# LED-Cube_Platine.net
KiCad netlist of a schematic drawn in EAGLE
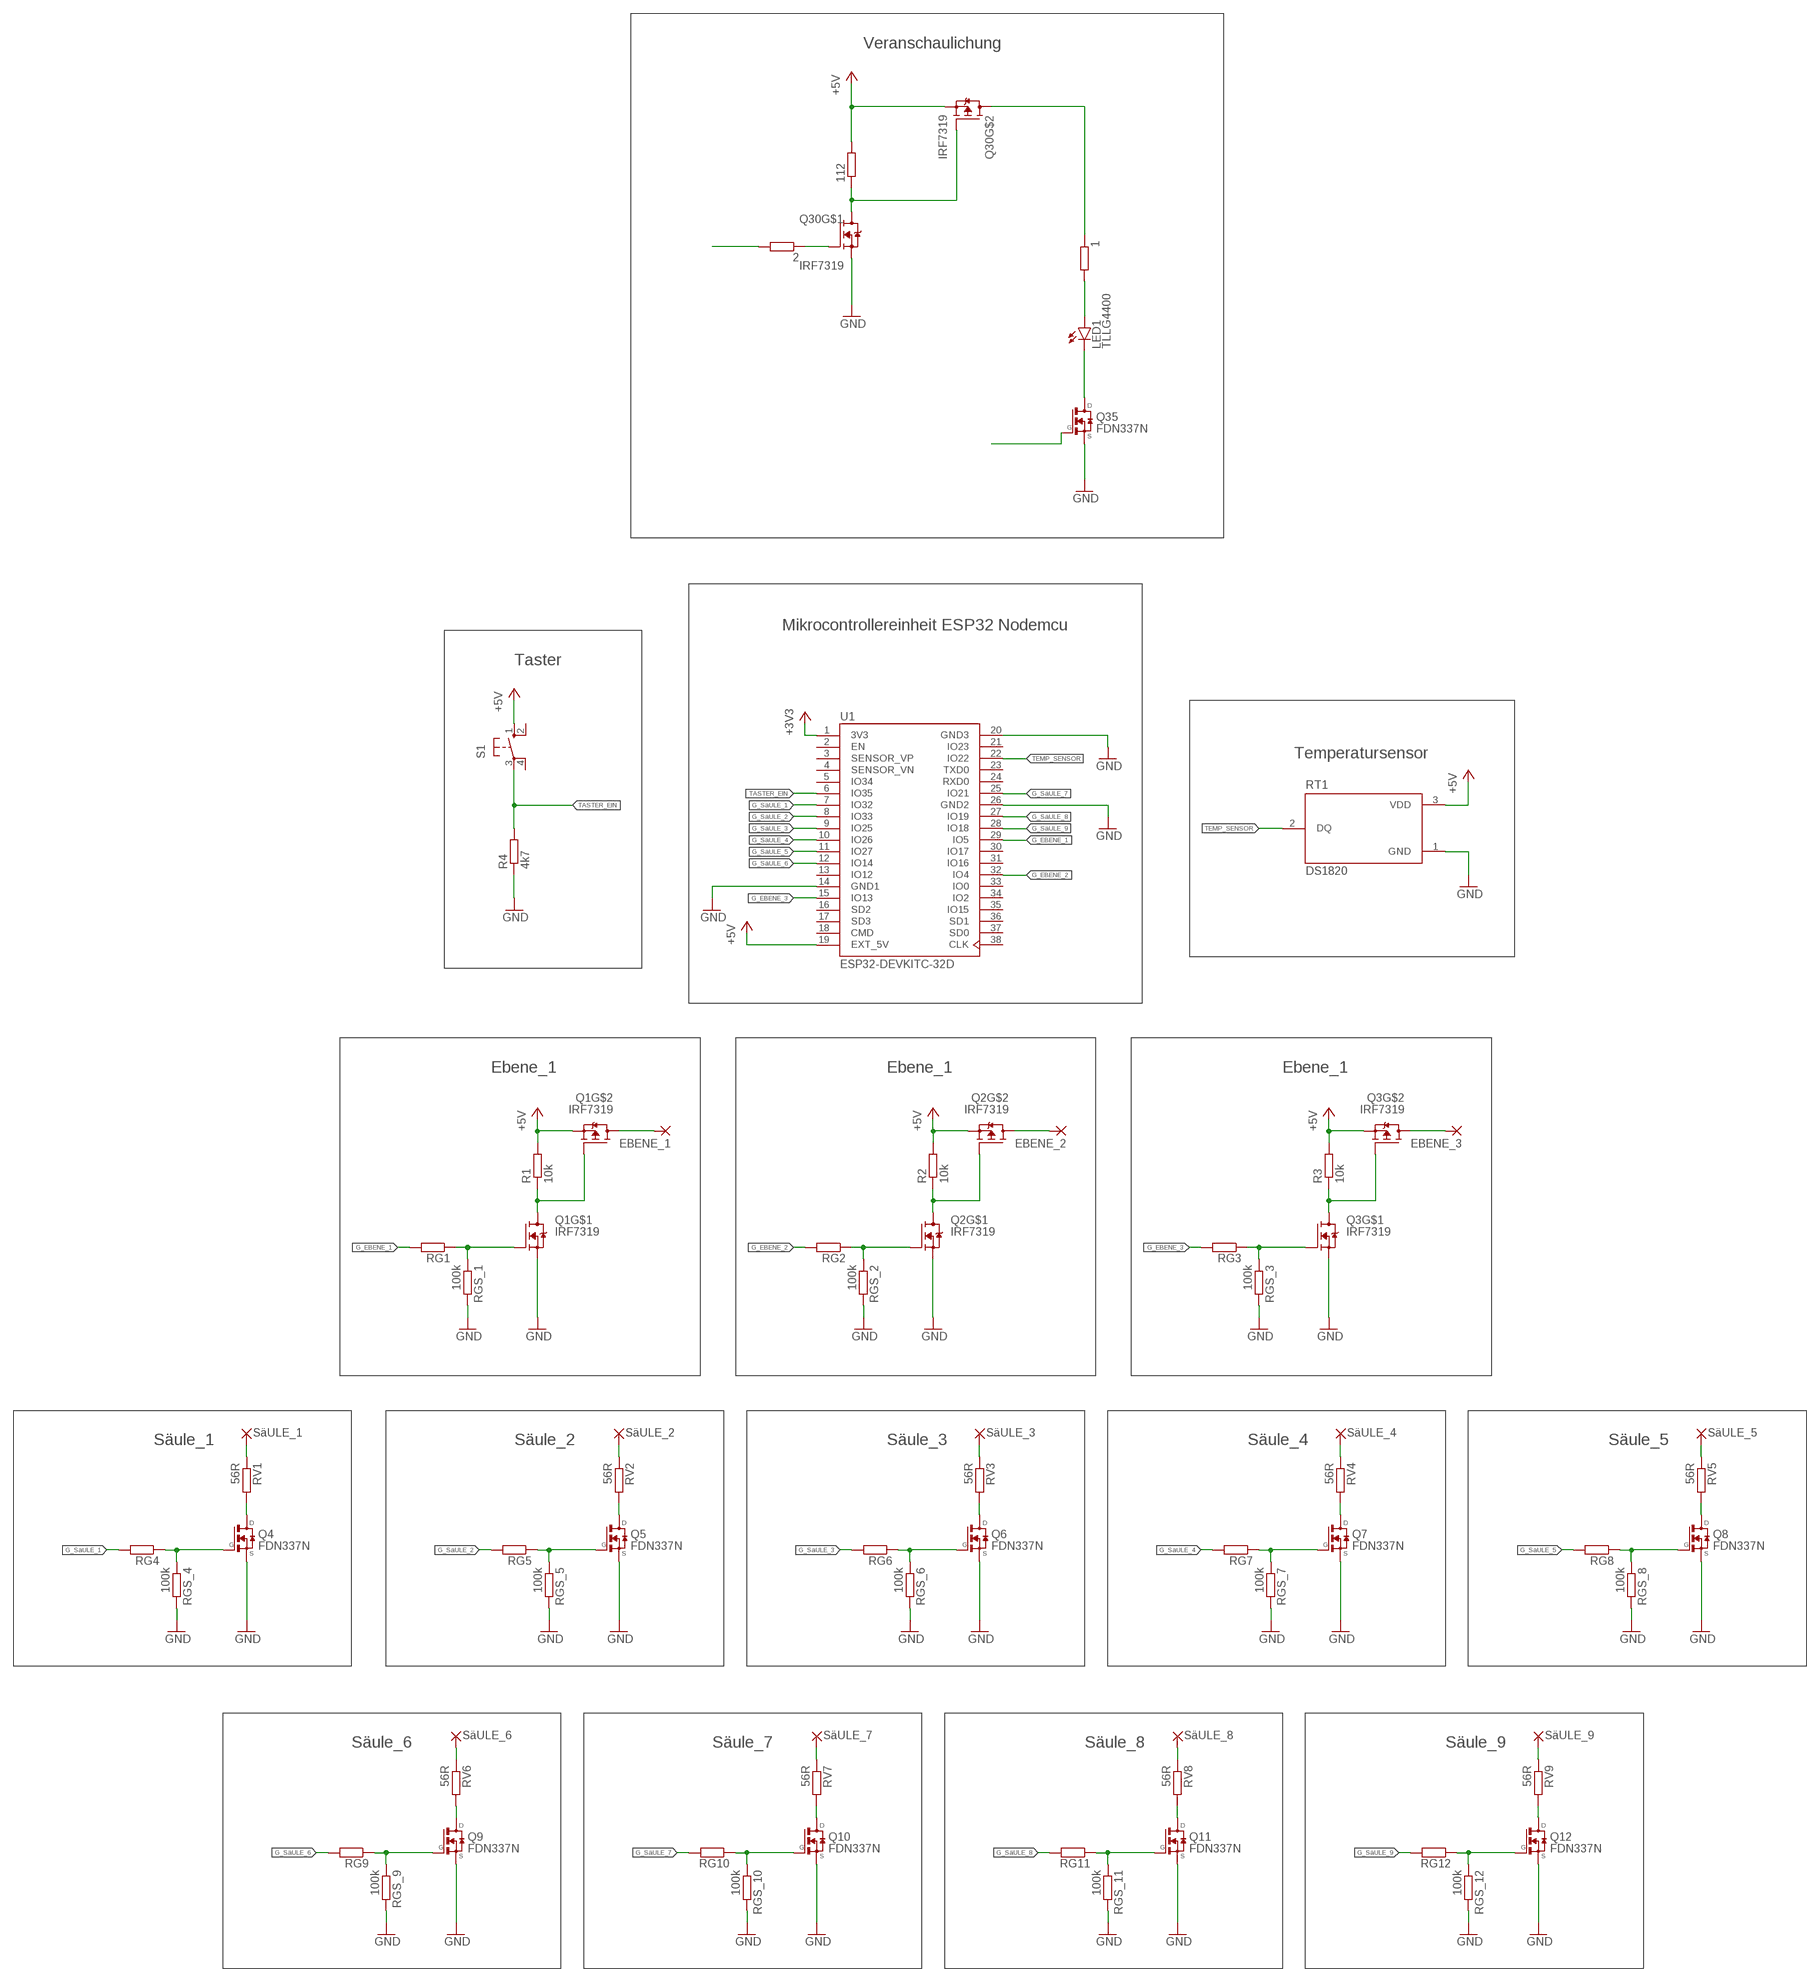
[diagram p0: schematic, sheet 1]

(export (version "E")
  (design (tool "Eeschema 10.0.6"))
  (components
    (comp (ref "1")
      (value "R-EU_R0805")
      (footprint "eagle-import:R0805")
      (libsource (lib "eagle-import") (part "R-EU_R0805"))
    )
    (comp (ref "2")
      (value "R-EU_R0805")
      (footprint "eagle-import:R0805")
      (libsource (lib "eagle-import") (part "R-EU_R0805"))
    )
    (comp (ref "112")
      (value "R-EU_R0805")
      (footprint "eagle-import:R0805")
      (libsource (lib "eagle-import") (part "R-EU_R0805"))
    )
    (comp (ref "EBENE_1")
      (value "WIREPAD1,6/0,8")
      (footprint "eagle-import:1,6_0,8")
      (libsource (lib "eagle-import") (part "WIREPAD1,6/0,8"))
    )
    (comp (ref "EBENE_2")
      (value "WIREPAD1,6/0,8")
      (footprint "eagle-import:1,6_0,8")
      (libsource (lib "eagle-import") (part "WIREPAD1,6/0,8"))
    )
    (comp (ref "EBENE_3")
      (value "WIREPAD1,6/0,8")
      (footprint "eagle-import:1,6_0,8")
      (libsource (lib "eagle-import") (part "WIREPAD1,6/0,8"))
    )
    (comp (ref "LED1")
      (value "TLLG4400")
      (footprint "eagle-import:LED3MM")
      (fields (field (name "MF") "VISHAY SEMICONDUCTOR"))
      (libsource (lib "eagle-import") (part "TLLG4400"))
    )
    (comp (ref "Q1")
      (value "IRF7319")
      (footprint "eagle-import:SOIC127P600X175-8N")
      (fields (field (name "MF") "Infineon Technologies"))
      (libsource (lib "eagle-import") (part "IRF7319"))
    )
    (comp (ref "Q2")
      (value "IRF7319")
      (footprint "eagle-import:SOIC127P600X175-8N")
      (fields (field (name "MF") "Infineon Technologies"))
      (libsource (lib "eagle-import") (part "IRF7319"))
    )
    (comp (ref "Q3")
      (value "IRF7319")
      (footprint "eagle-import:SOIC127P600X175-8N")
      (fields (field (name "MF") "Infineon Technologies"))
      (libsource (lib "eagle-import") (part "IRF7319"))
    )
    (comp (ref "Q4")
      (value "FDN337N")
      (footprint "eagle-import:SSOT-3")
      (fields (field (name "MF") "ON Semiconductor"))
      (libsource (lib "eagle-import") (part "FDN337N"))
    )
    (comp (ref "Q5")
      (value "FDN337N")
      (footprint "eagle-import:SSOT-3")
      (fields (field (name "MF") "ON Semiconductor"))
      (libsource (lib "eagle-import") (part "FDN337N"))
    )
    (comp (ref "Q6")
      (value "FDN337N")
      (footprint "eagle-import:SSOT-3")
      (fields (field (name "MF") "ON Semiconductor"))
      (libsource (lib "eagle-import") (part "FDN337N"))
    )
    (comp (ref "Q7")
      (value "FDN337N")
      (footprint "eagle-import:SSOT-3")
      (fields (field (name "MF") "ON Semiconductor"))
      (libsource (lib "eagle-import") (part "FDN337N"))
    )
    (comp (ref "Q8")
      (value "FDN337N")
      (footprint "eagle-import:SSOT-3")
      (fields (field (name "MF") "ON Semiconductor"))
      (libsource (lib "eagle-import") (part "FDN337N"))
    )
    (comp (ref "Q9")
      (value "FDN337N")
      (footprint "eagle-import:SSOT-3")
      (fields (field (name "MF") "ON Semiconductor"))
      (libsource (lib "eagle-import") (part "FDN337N"))
    )
    (comp (ref "Q10")
      (value "FDN337N")
      (footprint "eagle-import:SSOT-3")
      (fields (field (name "MF") "ON Semiconductor"))
      (libsource (lib "eagle-import") (part "FDN337N"))
    )
    (comp (ref "Q11")
      (value "FDN337N")
      (footprint "eagle-import:SSOT-3")
      (fields (field (name "MF") "ON Semiconductor"))
      (libsource (lib "eagle-import") (part "FDN337N"))
    )
    (comp (ref "Q12")
      (value "FDN337N")
      (footprint "eagle-import:SSOT-3")
      (fields (field (name "MF") "ON Semiconductor"))
      (libsource (lib "eagle-import") (part "FDN337N"))
    )
    (comp (ref "Q30")
      (value "IRF7319")
      (footprint "eagle-import:SOIC127P600X175-8N")
      (fields (field (name "MF") "Infineon Technologies"))
      (libsource (lib "eagle-import") (part "IRF7319"))
    )
    (comp (ref "Q35")
      (value "FDN337N")
      (footprint "eagle-import:SSOT-3")
      (fields (field (name "MF") "ON Semiconductor"))
      (libsource (lib "eagle-import") (part "FDN337N"))
    )
    (comp (ref "R1")
      (value "10k")
      (footprint "eagle-import:R0805")
      (libsource (lib "eagle-import") (part "R-EU_R0805"))
    )
    (comp (ref "R2")
      (value "10k")
      (footprint "eagle-import:R0805")
      (libsource (lib "eagle-import") (part "R-EU_R0805"))
    )
    (comp (ref "R3")
      (value "10k")
      (footprint "eagle-import:R0805")
      (libsource (lib "eagle-import") (part "R-EU_R0805"))
    )
    (comp (ref "R4")
      (value "4k7")
      (footprint "eagle-import:R0805")
      (libsource (lib "eagle-import") (part "R-EU_R0805"))
    )
    (comp (ref "RG1")
      (value "R-EU_R0805")
      (footprint "eagle-import:R0805")
      (libsource (lib "eagle-import") (part "R-EU_R0805"))
    )
    (comp (ref "RG2")
      (value "R-EU_R0805")
      (footprint "eagle-import:R0805")
      (libsource (lib "eagle-import") (part "R-EU_R0805"))
    )
    (comp (ref "RG3")
      (value "R-EU_R0805")
      (footprint "eagle-import:R0805")
      (libsource (lib "eagle-import") (part "R-EU_R0805"))
    )
    (comp (ref "RG4")
      (value "R-EU_R0805")
      (footprint "eagle-import:R0805")
      (libsource (lib "eagle-import") (part "R-EU_R0805"))
    )
    (comp (ref "RG5")
      (value "R-EU_R0805")
      (footprint "eagle-import:R0805")
      (libsource (lib "eagle-import") (part "R-EU_R0805"))
    )
    (comp (ref "RG6")
      (value "R-EU_R0805")
      (footprint "eagle-import:R0805")
      (libsource (lib "eagle-import") (part "R-EU_R0805"))
    )
    (comp (ref "RG7")
      (value "R-EU_R0805")
      (footprint "eagle-import:R0805")
      (libsource (lib "eagle-import") (part "R-EU_R0805"))
    )
    (comp (ref "RG8")
      (value "R-EU_R0805")
      (footprint "eagle-import:R0805")
      (libsource (lib "eagle-import") (part "R-EU_R0805"))
    )
    (comp (ref "RG9")
      (value "R-EU_R0805")
      (footprint "eagle-import:R0805")
      (libsource (lib "eagle-import") (part "R-EU_R0805"))
    )
    (comp (ref "RG10")
      (value "R-EU_R0805")
      (footprint "eagle-import:R0805")
      (libsource (lib "eagle-import") (part "R-EU_R0805"))
    )
    (comp (ref "RG11")
      (value "R-EU_R0805")
      (footprint "eagle-import:R0805")
      (libsource (lib "eagle-import") (part "R-EU_R0805"))
    )
    (comp (ref "RG12")
      (value "R-EU_R0805")
      (footprint "eagle-import:R0805")
      (libsource (lib "eagle-import") (part "R-EU_R0805"))
    )
    (comp (ref "RGS_1")
      (value "100k")
      (footprint "eagle-import:R0805")
      (libsource (lib "eagle-import") (part "R-EU_R0805"))
    )
    (comp (ref "RGS_2")
      (value "100k")
      (footprint "eagle-import:R0805")
      (libsource (lib "eagle-import") (part "R-EU_R0805"))
    )
    (comp (ref "RGS_3")
      (value "100k")
      (footprint "eagle-import:R0805")
      (libsource (lib "eagle-import") (part "R-EU_R0805"))
    )
    (comp (ref "RGS_4")
      (value "100k")
      (footprint "eagle-import:R0805")
      (libsource (lib "eagle-import") (part "R-EU_R0805"))
    )
    (comp (ref "RGS_5")
      (value "100k")
      (footprint "eagle-import:R0805")
      (libsource (lib "eagle-import") (part "R-EU_R0805"))
    )
    (comp (ref "RGS_6")
      (value "100k")
      (footprint "eagle-import:R0805")
      (libsource (lib "eagle-import") (part "R-EU_R0805"))
    )
    (comp (ref "RGS_7")
      (value "100k")
      (footprint "eagle-import:R0805")
      (libsource (lib "eagle-import") (part "R-EU_R0805"))
    )
    (comp (ref "RGS_8")
      (value "100k")
      (footprint "eagle-import:R0805")
      (libsource (lib "eagle-import") (part "R-EU_R0805"))
    )
    (comp (ref "RGS_9")
      (value "100k")
      (footprint "eagle-import:R0805")
      (libsource (lib "eagle-import") (part "R-EU_R0805"))
    )
    (comp (ref "RGS_10")
      (value "100k")
      (footprint "eagle-import:R0805")
      (libsource (lib "eagle-import") (part "R-EU_R0805"))
    )
    (comp (ref "RGS_11")
      (value "100k")
      (footprint "eagle-import:R0805")
      (libsource (lib "eagle-import") (part "R-EU_R0805"))
    )
    (comp (ref "RGS_12")
      (value "100k")
      (footprint "eagle-import:R0805")
      (libsource (lib "eagle-import") (part "R-EU_R0805"))
    )
    (comp (ref "RT1")
      (value "DS1820")
      (footprint "eagle-import:TO92127P495H695-3")
      (fields (field (name "MF") "Maxim Integrated"))
      (libsource (lib "eagle-import") (part "DS1820"))
    )
    (comp (ref "RV1")
      (value "56R")
      (footprint "eagle-import:R0805")
      (libsource (lib "eagle-import") (part "R-EU_R0805"))
    )
    (comp (ref "RV2")
      (value "56R")
      (footprint "eagle-import:R0805")
      (libsource (lib "eagle-import") (part "R-EU_R0805"))
    )
    (comp (ref "RV3")
      (value "56R")
      (footprint "eagle-import:R0805")
      (libsource (lib "eagle-import") (part "R-EU_R0805"))
    )
    (comp (ref "RV4")
      (value "56R")
      (footprint "eagle-import:R0805")
      (libsource (lib "eagle-import") (part "R-EU_R0805"))
    )
    (comp (ref "RV5")
      (value "56R")
      (footprint "eagle-import:R0805")
      (libsource (lib "eagle-import") (part "R-EU_R0805"))
    )
    (comp (ref "RV6")
      (value "56R")
      (footprint "eagle-import:R0805")
      (libsource (lib "eagle-import") (part "R-EU_R0805"))
    )
    (comp (ref "RV7")
      (value "56R")
      (footprint "eagle-import:R0805")
      (libsource (lib "eagle-import") (part "R-EU_R0805"))
    )
    (comp (ref "RV8")
      (value "56R")
      (footprint "eagle-import:R0805")
      (libsource (lib "eagle-import") (part "R-EU_R0805"))
    )
    (comp (ref "RV9")
      (value "56R")
      (footprint "eagle-import:R0805")
      (libsource (lib "eagle-import") (part "R-EU_R0805"))
    )
    (comp (ref "S1")
      (value "10-XX")
      (footprint "eagle-import:B3F-10XX")
      (fields (field (name "MPN") "B3F-1000"))
      (libsource (lib "eagle-import") (part "10-XX"))
    )
    (comp (ref "SäULE_1")
      (value "WIREPAD1,6/0,8")
      (footprint "eagle-import:1,6_0,8")
      (libsource (lib "eagle-import") (part "WIREPAD1,6/0,8"))
    )
    (comp (ref "SäULE_2")
      (value "WIREPAD1,6/0,8")
      (footprint "eagle-import:1,6_0,8")
      (libsource (lib "eagle-import") (part "WIREPAD1,6/0,8"))
    )
    (comp (ref "SäULE_3")
      (value "WIREPAD1,6/0,8")
      (footprint "eagle-import:1,6_0,8")
      (libsource (lib "eagle-import") (part "WIREPAD1,6/0,8"))
    )
    (comp (ref "SäULE_4")
      (value "WIREPAD1,6/0,8")
      (footprint "eagle-import:1,6_0,8")
      (libsource (lib "eagle-import") (part "WIREPAD1,6/0,8"))
    )
    (comp (ref "SäULE_5")
      (value "WIREPAD1,6/0,8")
      (footprint "eagle-import:1,6_0,8")
      (libsource (lib "eagle-import") (part "WIREPAD1,6/0,8"))
    )
    (comp (ref "SäULE_6")
      (value "WIREPAD1,6/0,8")
      (footprint "eagle-import:1,6_0,8")
      (libsource (lib "eagle-import") (part "WIREPAD1,6/0,8"))
    )
    (comp (ref "SäULE_7")
      (value "WIREPAD1,6/0,8")
      (footprint "eagle-import:1,6_0,8")
      (libsource (lib "eagle-import") (part "WIREPAD1,6/0,8"))
    )
    (comp (ref "SäULE_8")
      (value "WIREPAD1,6/0,8")
      (footprint "eagle-import:1,6_0,8")
      (libsource (lib "eagle-import") (part "WIREPAD1,6/0,8"))
    )
    (comp (ref "SäULE_9")
      (value "WIREPAD1,6/0,8")
      (footprint "eagle-import:1,6_0,8")
      (libsource (lib "eagle-import") (part "WIREPAD1,6/0,8"))
    )
    (comp (ref "U1")
      (value "ESP32-DEVKITC-32D")
      (footprint "eagle-import:MODULE_ESP32-DEVKITC-32D")
      (fields (field (name "MF") "Espressif Systems"))
      (libsource (lib "eagle-import") (part "ESP32-DEVKITC-32D"))
    )
  )
  (nets
    (net (code "1") (name "+3V3") (class "Default")
      (node (ref "U1") (pin "1") (pinfunction "3V3_1") (pintype "power_in"))
    )
    (net (code "2") (name "+5V") (class "Default")
      (node (ref "112") (pin "2") (pinfunction "2_2") (pintype "passive"))
      (node (ref "Q1") (pin "3") (pinfunction "S2_3") (pintype "passive"))
      (node (ref "Q2") (pin "3") (pinfunction "S2_3") (pintype "passive"))
      (node (ref "Q3") (pin "3") (pinfunction "S2_3") (pintype "passive"))
      (node (ref "Q30") (pin "3") (pinfunction "S2_3") (pintype "passive"))
      (node (ref "R1") (pin "2") (pinfunction "2_2") (pintype "passive"))
      (node (ref "R2") (pin "2") (pinfunction "2_2") (pintype "passive"))
      (node (ref "R3") (pin "2") (pinfunction "2_2") (pintype "passive"))
      (node (ref "RT1") (pin "3") (pinfunction "VDD_3") (pintype "power_in"))
      (node (ref "S1") (pin "1") (pinfunction "S_1") (pintype "passive"))
      (node (ref "U1") (pin "19") (pinfunction "EXT_5V_19") (pintype "power_in"))
    )
    (net (code "3") (name "GND") (class "Default")
      (node (ref "Q1") (pin "1") (pinfunction "S1_1") (pintype "passive"))
      (node (ref "Q10") (pin "2") (pinfunction "S_2") (pintype "passive"))
      (node (ref "Q11") (pin "2") (pinfunction "S_2") (pintype "passive"))
      (node (ref "Q12") (pin "2") (pinfunction "S_2") (pintype "passive"))
      (node (ref "Q2") (pin "1") (pinfunction "S1_1") (pintype "passive"))
      (node (ref "Q3") (pin "1") (pinfunction "S1_1") (pintype "passive"))
      (node (ref "Q30") (pin "1") (pinfunction "S1_1") (pintype "passive"))
      (node (ref "Q35") (pin "2") (pinfunction "S_2") (pintype "passive"))
      (node (ref "Q4") (pin "2") (pinfunction "S_2") (pintype "passive"))
      (node (ref "Q5") (pin "2") (pinfunction "S_2") (pintype "passive"))
      (node (ref "Q6") (pin "2") (pinfunction "S_2") (pintype "passive"))
      (node (ref "Q7") (pin "2") (pinfunction "S_2") (pintype "passive"))
      (node (ref "Q8") (pin "2") (pinfunction "S_2") (pintype "passive"))
      (node (ref "Q9") (pin "2") (pinfunction "S_2") (pintype "passive"))
      (node (ref "R4") (pin "1") (pinfunction "1_1") (pintype "passive"))
      (node (ref "RGS_1") (pin "2") (pinfunction "2_2") (pintype "passive"))
      (node (ref "RGS_10") (pin "2") (pinfunction "2_2") (pintype "passive"))
      (node (ref "RGS_11") (pin "2") (pinfunction "2_2") (pintype "passive"))
      (node (ref "RGS_12") (pin "2") (pinfunction "2_2") (pintype "passive"))
      (node (ref "RGS_2") (pin "2") (pinfunction "2_2") (pintype "passive"))
      (node (ref "RGS_3") (pin "2") (pinfunction "2_2") (pintype "passive"))
      (node (ref "RGS_4") (pin "2") (pinfunction "2_2") (pintype "passive"))
      (node (ref "RGS_5") (pin "2") (pinfunction "2_2") (pintype "passive"))
      (node (ref "RGS_6") (pin "2") (pinfunction "2_2") (pintype "passive"))
      (node (ref "RGS_7") (pin "2") (pinfunction "2_2") (pintype "passive"))
      (node (ref "RGS_8") (pin "2") (pinfunction "2_2") (pintype "passive"))
      (node (ref "RGS_9") (pin "2") (pinfunction "2_2") (pintype "passive"))
      (node (ref "RT1") (pin "1") (pinfunction "GND_1") (pintype "power_in"))
      (node (ref "U1") (pin "14") (pinfunction "GND1_14") (pintype "power_in"))
      (node (ref "U1") (pin "20") (pinfunction "GND3_20") (pintype "power_in"))
      (node (ref "U1") (pin "26") (pinfunction "GND2_26") (pintype "power_in"))
    )
    (net (code "4") (name "G_EBENE_1") (class "Default")
      (node (ref "RG1") (pin "2") (pinfunction "2_2") (pintype "passive"))
      (node (ref "U1") (pin "29") (pinfunction "IO5_29") (pintype "bidirectional"))
    )
    (net (code "5") (name "G_EBENE_2") (class "Default")
      (node (ref "RG2") (pin "2") (pinfunction "2_2") (pintype "passive"))
      (node (ref "U1") (pin "32") (pinfunction "IO4_32") (pintype "bidirectional"))
    )
    (net (code "6") (name "G_EBENE_3") (class "Default")
      (node (ref "RG3") (pin "2") (pinfunction "2_2") (pintype "passive"))
      (node (ref "U1") (pin "15") (pinfunction "IO13_15") (pintype "bidirectional"))
    )
    (net (code "7") (name "G_SäULE_1") (class "Default")
      (node (ref "RG4") (pin "2") (pinfunction "2_2") (pintype "passive"))
      (node (ref "U1") (pin "7") (pinfunction "IO32_7") (pintype "bidirectional"))
    )
    (net (code "8") (name "G_SäULE_2") (class "Default")
      (node (ref "RG5") (pin "2") (pinfunction "2_2") (pintype "passive"))
      (node (ref "U1") (pin "8") (pinfunction "IO33_8") (pintype "bidirectional"))
    )
    (net (code "9") (name "G_SäULE_3") (class "Default")
      (node (ref "RG6") (pin "2") (pinfunction "2_2") (pintype "passive"))
      (node (ref "U1") (pin "9") (pinfunction "IO25_9") (pintype "bidirectional"))
    )
    (net (code "10") (name "G_SäULE_4") (class "Default")
      (node (ref "RG7") (pin "2") (pinfunction "2_2") (pintype "passive"))
      (node (ref "U1") (pin "10") (pinfunction "IO26_10") (pintype "bidirectional"))
    )
    (net (code "11") (name "G_SäULE_5") (class "Default")
      (node (ref "RG8") (pin "2") (pinfunction "2_2") (pintype "passive"))
      (node (ref "U1") (pin "11") (pinfunction "IO27_11") (pintype "bidirectional"))
    )
    (net (code "12") (name "G_SäULE_6") (class "Default")
      (node (ref "RG9") (pin "2") (pinfunction "2_2") (pintype "passive"))
      (node (ref "U1") (pin "12") (pinfunction "IO14_12") (pintype "bidirectional"))
    )
    (net (code "13") (name "G_SäULE_7") (class "Default")
      (node (ref "RG10") (pin "2") (pinfunction "2_2") (pintype "passive"))
      (node (ref "U1") (pin "25") (pinfunction "IO21_25") (pintype "bidirectional"))
    )
    (net (code "14") (name "G_SäULE_8") (class "Default")
      (node (ref "RG11") (pin "2") (pinfunction "2_2") (pintype "passive"))
      (node (ref "U1") (pin "27") (pinfunction "IO19_27") (pintype "bidirectional"))
    )
    (net (code "15") (name "G_SäULE_9") (class "Default")
      (node (ref "RG12") (pin "2") (pinfunction "2_2") (pintype "passive"))
      (node (ref "U1") (pin "28") (pinfunction "IO18_28") (pintype "bidirectional"))
    )
    (net (code "16") (name "Net-(1-Pad1)") (class "Default")
      (node (ref "1") (pin "1") (pinfunction "1_1") (pintype "passive"))
      (node (ref "Q30") (pin "5") (pinfunction "D2_5") (pintype "passive"))
      (node (ref "Q30") (pin "6") (pinfunction "D2_6") (pintype "passive"))
    )
    (net (code "17") (name "Net-(1-Pad2)") (class "Default")
      (node (ref "1") (pin "2") (pinfunction "2_2") (pintype "passive"))
      (node (ref "LED1") (pin "A") (pinfunction "A_A") (pintype "passive"))
    )
    (net (code "18") (name "Net-(EBENE_1-P)") (class "Default")
      (node (ref "EBENE_1") (pin "1") (pinfunction "P_1") (pintype "passive"))
      (node (ref "Q1") (pin "5") (pinfunction "D2_5") (pintype "passive"))
      (node (ref "Q1") (pin "6") (pinfunction "D2_6") (pintype "passive"))
    )
    (net (code "19") (name "Net-(EBENE_2-P)") (class "Default")
      (node (ref "EBENE_2") (pin "1") (pinfunction "P_1") (pintype "passive"))
      (node (ref "Q2") (pin "5") (pinfunction "D2_5") (pintype "passive"))
      (node (ref "Q2") (pin "6") (pinfunction "D2_6") (pintype "passive"))
    )
    (net (code "20") (name "Net-(EBENE_3-P)") (class "Default")
      (node (ref "EBENE_3") (pin "1") (pinfunction "P_1") (pintype "passive"))
      (node (ref "Q3") (pin "5") (pinfunction "D2_5") (pintype "passive"))
      (node (ref "Q3") (pin "6") (pinfunction "D2_6") (pintype "passive"))
    )
    (net (code "21") (name "Net-(LED1-C)") (class "Default")
      (node (ref "LED1") (pin "K") (pinfunction "C_K") (pintype "passive"))
      (node (ref "Q35") (pin "3") (pinfunction "D_3") (pintype "passive"))
    )
    (net (code "22") (name "Net-(Q1A-G1)") (class "Default")
      (node (ref "Q1") (pin "2") (pinfunction "G1_2") (pintype "passive"))
      (node (ref "RG1") (pin "1") (pinfunction "1_1") (pintype "passive"))
      (node (ref "RGS_1") (pin "1") (pinfunction "1_1") (pintype "passive"))
    )
    (net (code "23") (name "Net-(Q1B-G2)") (class "Default")
      (node (ref "Q1") (pin "4") (pinfunction "G2_4") (pintype "passive"))
      (node (ref "Q1") (pin "7") (pinfunction "D1_7") (pintype "passive"))
      (node (ref "Q1") (pin "8") (pinfunction "D1_8") (pintype "passive"))
      (node (ref "R1") (pin "1") (pinfunction "1_1") (pintype "passive"))
    )
    (net (code "24") (name "Net-(Q2A-G1)") (class "Default")
      (node (ref "Q2") (pin "2") (pinfunction "G1_2") (pintype "passive"))
      (node (ref "RG2") (pin "1") (pinfunction "1_1") (pintype "passive"))
      (node (ref "RGS_2") (pin "1") (pinfunction "1_1") (pintype "passive"))
    )
    (net (code "25") (name "Net-(Q2B-G2)") (class "Default")
      (node (ref "Q2") (pin "4") (pinfunction "G2_4") (pintype "passive"))
      (node (ref "Q2") (pin "7") (pinfunction "D1_7") (pintype "passive"))
      (node (ref "Q2") (pin "8") (pinfunction "D1_8") (pintype "passive"))
      (node (ref "R2") (pin "1") (pinfunction "1_1") (pintype "passive"))
    )
    (net (code "26") (name "Net-(Q3A-G1)") (class "Default")
      (node (ref "Q3") (pin "2") (pinfunction "G1_2") (pintype "passive"))
      (node (ref "RG3") (pin "1") (pinfunction "1_1") (pintype "passive"))
      (node (ref "RGS_3") (pin "1") (pinfunction "1_1") (pintype "passive"))
    )
    (net (code "27") (name "Net-(Q3B-G2)") (class "Default")
      (node (ref "Q3") (pin "4") (pinfunction "G2_4") (pintype "passive"))
      (node (ref "Q3") (pin "7") (pinfunction "D1_7") (pintype "passive"))
      (node (ref "Q3") (pin "8") (pinfunction "D1_8") (pintype "passive"))
      (node (ref "R3") (pin "1") (pinfunction "1_1") (pintype "passive"))
    )
    (net (code "28") (name "Net-(Q4-D)") (class "Default")
      (node (ref "Q4") (pin "3") (pinfunction "D_3") (pintype "passive"))
      (node (ref "RV1") (pin "2") (pinfunction "2_2") (pintype "passive"))
    )
    (net (code "29") (name "Net-(Q4-G)") (class "Default")
      (node (ref "Q4") (pin "1") (pinfunction "G_1") (pintype "passive"))
      (node (ref "RG4") (pin "1") (pinfunction "1_1") (pintype "passive"))
      (node (ref "RGS_4") (pin "1") (pinfunction "1_1") (pintype "passive"))
    )
    (net (code "30") (name "Net-(Q5-D)") (class "Default")
      (node (ref "Q5") (pin "3") (pinfunction "D_3") (pintype "passive"))
      (node (ref "RV2") (pin "2") (pinfunction "2_2") (pintype "passive"))
    )
    (net (code "31") (name "Net-(Q5-G)") (class "Default")
      (node (ref "Q5") (pin "1") (pinfunction "G_1") (pintype "passive"))
      (node (ref "RG5") (pin "1") (pinfunction "1_1") (pintype "passive"))
      (node (ref "RGS_5") (pin "1") (pinfunction "1_1") (pintype "passive"))
    )
    (net (code "32") (name "Net-(Q6-D)") (class "Default")
      (node (ref "Q6") (pin "3") (pinfunction "D_3") (pintype "passive"))
      (node (ref "RV3") (pin "2") (pinfunction "2_2") (pintype "passive"))
    )
    (net (code "33") (name "Net-(Q6-G)") (class "Default")
      (node (ref "Q6") (pin "1") (pinfunction "G_1") (pintype "passive"))
      (node (ref "RG6") (pin "1") (pinfunction "1_1") (pintype "passive"))
      (node (ref "RGS_6") (pin "1") (pinfunction "1_1") (pintype "passive"))
    )
    (net (code "34") (name "Net-(Q7-D)") (class "Default")
      (node (ref "Q7") (pin "3") (pinfunction "D_3") (pintype "passive"))
      (node (ref "RV4") (pin "2") (pinfunction "2_2") (pintype "passive"))
    )
    (net (code "35") (name "Net-(Q7-G)") (class "Default")
      (node (ref "Q7") (pin "1") (pinfunction "G_1") (pintype "passive"))
      (node (ref "RG7") (pin "1") (pinfunction "1_1") (pintype "passive"))
      (node (ref "RGS_7") (pin "1") (pinfunction "1_1") (pintype "passive"))
    )
    (net (code "36") (name "Net-(Q8-D)") (class "Default")
      (node (ref "Q8") (pin "3") (pinfunction "D_3") (pintype "passive"))
      (node (ref "RV5") (pin "2") (pinfunction "2_2") (pintype "passive"))
    )
    (net (code "37") (name "Net-(Q8-G)") (class "Default")
      (node (ref "Q8") (pin "1") (pinfunction "G_1") (pintype "passive"))
      (node (ref "RG8") (pin "1") (pinfunction "1_1") (pintype "passive"))
      (node (ref "RGS_8") (pin "1") (pinfunction "1_1") (pintype "passive"))
    )
    (net (code "38") (name "Net-(Q9-D)") (class "Default")
      (node (ref "Q9") (pin "3") (pinfunction "D_3") (pintype "passive"))
      (node (ref "RV6") (pin "2") (pinfunction "2_2") (pintype "passive"))
    )
    (net (code "39") (name "Net-(Q9-G)") (class "Default")
      (node (ref "Q9") (pin "1") (pinfunction "G_1") (pintype "passive"))
      (node (ref "RG9") (pin "1") (pinfunction "1_1") (pintype "passive"))
      (node (ref "RGS_9") (pin "1") (pinfunction "1_1") (pintype "passive"))
    )
    (net (code "40") (name "Net-(Q10-D)") (class "Default")
      (node (ref "Q10") (pin "3") (pinfunction "D_3") (pintype "passive"))
      (node (ref "RV7") (pin "2") (pinfunction "2_2") (pintype "passive"))
    )
    (net (code "41") (name "Net-(Q10-G)") (class "Default")
      (node (ref "Q10") (pin "1") (pinfunction "G_1") (pintype "passive"))
      (node (ref "RG10") (pin "1") (pinfunction "1_1") (pintype "passive"))
      (node (ref "RGS_10") (pin "1") (pinfunction "1_1") (pintype "passive"))
    )
    (net (code "42") (name "Net-(Q11-D)") (class "Default")
      (node (ref "Q11") (pin "3") (pinfunction "D_3") (pintype "passive"))
      (node (ref "RV8") (pin "2") (pinfunction "2_2") (pintype "passive"))
    )
    (net (code "43") (name "Net-(Q11-G)") (class "Default")
      (node (ref "Q11") (pin "1") (pinfunction "G_1") (pintype "passive"))
      (node (ref "RG11") (pin "1") (pinfunction "1_1") (pintype "passive"))
      (node (ref "RGS_11") (pin "1") (pinfunction "1_1") (pintype "passive"))
    )
    (net (code "44") (name "Net-(Q12-D)") (class "Default")
      (node (ref "Q12") (pin "3") (pinfunction "D_3") (pintype "passive"))
      (node (ref "RV9") (pin "2") (pinfunction "2_2") (pintype "passive"))
    )
    (net (code "45") (name "Net-(Q12-G)") (class "Default")
      (node (ref "Q12") (pin "1") (pinfunction "G_1") (pintype "passive"))
      (node (ref "RG12") (pin "1") (pinfunction "1_1") (pintype "passive"))
      (node (ref "RGS_12") (pin "1") (pinfunction "1_1") (pintype "passive"))
    )
    (net (code "46") (name "Net-(Q30A-G1)") (class "Default")
      (node (ref "2") (pin "1") (pinfunction "1_1") (pintype "passive"))
      (node (ref "Q30") (pin "2") (pinfunction "G1_2") (pintype "passive"))
    )
    (net (code "47") (name "Net-(Q30B-G2)") (class "Default")
      (node (ref "112") (pin "1") (pinfunction "1_1") (pintype "passive"))
      (node (ref "Q30") (pin "4") (pinfunction "G2_4") (pintype "passive"))
      (node (ref "Q30") (pin "7") (pinfunction "D1_7") (pintype "passive"))
      (node (ref "Q30") (pin "8") (pinfunction "D1_8") (pintype "passive"))
    )
    (net (code "48") (name "Net-(SäULE_1-P)") (class "Default")
      (node (ref "RV1") (pin "1") (pinfunction "1_1") (pintype "passive"))
      (node (ref "SäULE_1") (pin "1") (pinfunction "P_1") (pintype "passive"))
    )
    (net (code "49") (name "Net-(SäULE_2-P)") (class "Default")
      (node (ref "RV2") (pin "1") (pinfunction "1_1") (pintype "passive"))
      (node (ref "SäULE_2") (pin "1") (pinfunction "P_1") (pintype "passive"))
    )
    (net (code "50") (name "Net-(SäULE_3-P)") (class "Default")
      (node (ref "RV3") (pin "1") (pinfunction "1_1") (pintype "passive"))
      (node (ref "SäULE_3") (pin "1") (pinfunction "P_1") (pintype "passive"))
    )
    (net (code "51") (name "Net-(SäULE_4-P)") (class "Default")
      (node (ref "RV4") (pin "1") (pinfunction "1_1") (pintype "passive"))
      (node (ref "SäULE_4") (pin "1") (pinfunction "P_1") (pintype "passive"))
    )
    (net (code "52") (name "Net-(SäULE_5-P)") (class "Default")
      (node (ref "RV5") (pin "1") (pinfunction "1_1") (pintype "passive"))
      (node (ref "SäULE_5") (pin "1") (pinfunction "P_1") (pintype "passive"))
    )
    (net (code "53") (name "Net-(SäULE_6-P)") (class "Default")
      (node (ref "RV6") (pin "1") (pinfunction "1_1") (pintype "passive"))
      (node (ref "SäULE_6") (pin "1") (pinfunction "P_1") (pintype "passive"))
    )
    (net (code "54") (name "Net-(SäULE_7-P)") (class "Default")
      (node (ref "RV7") (pin "1") (pinfunction "1_1") (pintype "passive"))
      (node (ref "SäULE_7") (pin "1") (pinfunction "P_1") (pintype "passive"))
    )
    (net (code "55") (name "Net-(SäULE_8-P)") (class "Default")
      (node (ref "RV8") (pin "1") (pinfunction "1_1") (pintype "passive"))
      (node (ref "SäULE_8") (pin "1") (pinfunction "P_1") (pintype "passive"))
    )
    (net (code "56") (name "Net-(SäULE_9-P)") (class "Default")
      (node (ref "RV9") (pin "1") (pinfunction "1_1") (pintype "passive"))
      (node (ref "SäULE_9") (pin "1") (pinfunction "P_1") (pintype "passive"))
    )
    (net (code "57") (name "TASTER_EIN") (class "Default")
      (node (ref "R4") (pin "2") (pinfunction "2_2") (pintype "passive"))
      (node (ref "S1") (pin "3") (pinfunction "P_3") (pintype "passive"))
      (node (ref "U1") (pin "6") (pinfunction "IO35_6") (pintype "bidirectional"))
    )
    (net (code "58") (name "TEMP_SENSOR") (class "Default")
      (node (ref "RT1") (pin "2") (pinfunction "DQ_2") (pintype "bidirectional"))
      (node (ref "U1") (pin "22") (pinfunction "IO22_22") (pintype "bidirectional"))
    )
    (net (code "59") (name "unconnected-(2-Pad2)") (class "Default")
      (node (ref "2") (pin "2") (pinfunction "2_2") (pintype "passive"))
    )
    (net (code "60") (name "unconnected-(Q35-G-Pad1)") (class "Default")
      (node (ref "Q35") (pin "1") (pinfunction "G_1") (pintype "passive"))
    )
    (net (code "61") (name "unconnected-(S1-P1-Pad4)") (class "Default")
      (node (ref "S1") (pin "4") (pinfunction "P1_4") (pintype "passive"))
    )
    (net (code "62") (name "unconnected-(S1-S1-Pad2)") (class "Default")
      (node (ref "S1") (pin "2") (pinfunction "S1_2") (pintype "passive"))
    )
    (net (code "63") (name "unconnected-(U1-CLK-Pad38)") (class "Default")
      (node (ref "U1") (pin "38") (pinfunction "CLK_38") (pintype "input"))
    )
    (net (code "64") (name "unconnected-(U1-CMD-Pad18)") (class "Default")
      (node (ref "U1") (pin "18") (pinfunction "CMD_18") (pintype "bidirectional"))
    )
    (net (code "65") (name "unconnected-(U1-EN-Pad2)") (class "Default")
      (node (ref "U1") (pin "2") (pinfunction "EN_2") (pintype "input"))
    )
    (net (code "66") (name "unconnected-(U1-IO0-Pad33)") (class "Default")
      (node (ref "U1") (pin "33") (pinfunction "IO0_33") (pintype "bidirectional"))
    )
    (net (code "67") (name "unconnected-(U1-IO2-Pad34)") (class "Default")
      (node (ref "U1") (pin "34") (pinfunction "IO2_34") (pintype "bidirectional"))
    )
    (net (code "68") (name "unconnected-(U1-IO12-Pad13)") (class "Default")
      (node (ref "U1") (pin "13") (pinfunction "IO12_13") (pintype "bidirectional"))
    )
    (net (code "69") (name "unconnected-(U1-IO15-Pad35)") (class "Default")
      (node (ref "U1") (pin "35") (pinfunction "IO15_35") (pintype "bidirectional"))
    )
    (net (code "70") (name "unconnected-(U1-IO16-Pad31)") (class "Default")
      (node (ref "U1") (pin "31") (pinfunction "IO16_31") (pintype "bidirectional"))
    )
    (net (code "71") (name "unconnected-(U1-IO17-Pad30)") (class "Default")
      (node (ref "U1") (pin "30") (pinfunction "IO17_30") (pintype "bidirectional"))
    )
    (net (code "72") (name "unconnected-(U1-IO23-Pad21)") (class "Default")
      (node (ref "U1") (pin "21") (pinfunction "IO23_21") (pintype "bidirectional"))
    )
    (net (code "73") (name "unconnected-(U1-IO34-Pad5)") (class "Default")
      (node (ref "U1") (pin "5") (pinfunction "IO34_5") (pintype "bidirectional"))
    )
    (net (code "74") (name "unconnected-(U1-RXD0-Pad24)") (class "Default")
      (node (ref "U1") (pin "24") (pinfunction "RXD0_24") (pintype "input"))
    )
    (net (code "75") (name "unconnected-(U1-SD0-Pad37)") (class "Default")
      (node (ref "U1") (pin "37") (pinfunction "SD0_37") (pintype "bidirectional"))
    )
    (net (code "76") (name "unconnected-(U1-SD1-Pad36)") (class "Default")
      (node (ref "U1") (pin "36") (pinfunction "SD1_36") (pintype "bidirectional"))
    )
    (net (code "77") (name "unconnected-(U1-SD2-Pad16)") (class "Default")
      (node (ref "U1") (pin "16") (pinfunction "SD2_16") (pintype "bidirectional"))
    )
    (net (code "78") (name "unconnected-(U1-SD3-Pad17)") (class "Default")
      (node (ref "U1") (pin "17") (pinfunction "SD3_17") (pintype "bidirectional"))
    )
    (net (code "79") (name "unconnected-(U1-SENSOR_VN-Pad4)") (class "Default")
      (node (ref "U1") (pin "4") (pinfunction "SENSOR_VN_4") (pintype "input"))
    )
    (net (code "80") (name "unconnected-(U1-SENSOR_VP-Pad3)") (class "Default")
      (node (ref "U1") (pin "3") (pinfunction "SENSOR_VP_3") (pintype "input"))
    )
    (net (code "81") (name "unconnected-(U1-TXD0-Pad23)") (class "Default")
      (node (ref "U1") (pin "23") (pinfunction "TXD0_23") (pintype "output"))
    )
  )
)
